# GD_Tcontroller_Front.net
KiCad netlist of a schematic drawn in Altium Designer
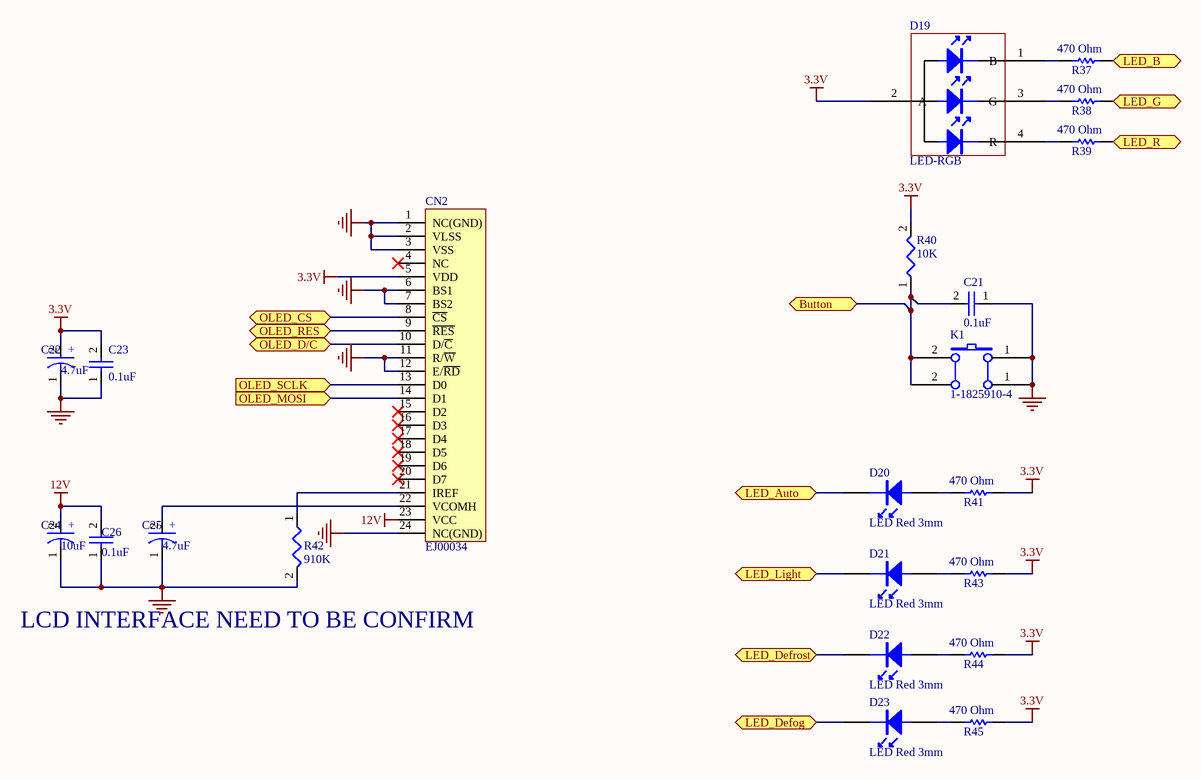
[diagram p0: GD_Tcontroller_Front.SchDoc]

(export (version "E")
  (design (tool "Eeschema 10.0.6"))
  (components
    (comp (ref "C21")
      (value "0.1uF")
      (footprint "C0805")
      (description "CAP SMD CR X7R 50V 10% 0.1uF 0805 ROHS")
      (fields (field (name "MANUFACTURER") "YAGEO") (field (name "Comment") "CAP"))
      (libsource (lib "enlogic") (part "CAP"))
    )
    (comp (ref "C22")
      (value "4.7uF")
      (footprint "TAN3216")
      (description "TAN 10uF 20% 10V 3216")
      (fields (field (name "MANUFACTURER") "AVX") (field (name "Comment") "CAPACITOR"))
      (libsource (lib "enlogic") (part "CAPACITOR"))
    )
    (comp (ref "C23")
      (value "0.1uF")
      (footprint "C0805")
      (description "CAP SMD CR X7R 50V 10% 0.1uF 0805 ROHS")
      (fields (field (name "MANUFACTURER") "YAGEO") (field (name "Comment") "CAP"))
      (libsource (lib "enlogic") (part "CAP"))
    )
    (comp (ref "C24")
      (value "10uF")
      (footprint "TAN6032")
      (description "CAP SMD Tan 35V 10% 10uF 2917 ROHS")
      (fields (field (name "MANUFACTURER") "AVX") (field (name "Comment") "CAPACITOR"))
      (libsource (lib "enlogic") (part "CAPACITOR"))
    )
    (comp (ref "C25")
      (value "4.7uF")
      (footprint "TAN6032")
      (description "CAP SMD Tan 35V 10% 4.7uF 2312 ROHS")
      (fields (field (name "MANUFACTURER") "AVX") (field (name "Comment") "CAPACITOR"))
      (libsource (lib "enlogic") (part "CAPACITOR"))
    )
    (comp (ref "C26")
      (value "0.1uF")
      (footprint "C0805")
      (description "CAP SMD CR X7R 50V 10% 0.1uF 0805 ROHS")
      (fields (field (name "MANUFACTURER") "YAGEO") (field (name "Comment") "CAP"))
      (libsource (lib "enlogic") (part "CAP"))
    )
    (comp (ref "CN2")
      (value "EJ00034")
      (footprint "PcbLib1:FPC24P0_5")
      (description "CONNECTOR FPC0.5MM 24PIN,0.4A,50V,SMT")
      (fields (field (name "MANUFACTURER") "FCI"))
      (libsource (lib "enlogic") (part "OLED_24-Pin"))
    )
    (comp (ref "D19")
      (value "LED-RGB")
      (footprint "LED-RGB-3528")
      (libsource (lib "Schlib1") (part "LED-RGB"))
    )
    (comp (ref "D20") (value "LED Red 3mm") (footprint "LED_DIP") (libsource (lib "*") (part "LED")))
    (comp (ref "D21") (value "LED Red 3mm") (footprint "LED_DIP") (libsource (lib "*") (part "LED")))
    (comp (ref "D22") (value "LED Red 3mm") (footprint "LED_DIP") (libsource (lib "*") (part "LED")))
    (comp (ref "D23") (value "LED Red 3mm") (footprint "LED_DIP") (libsource (lib "*") (part "LED")))
    (comp (ref "K1")
      (value "1-1825910-4")
      (footprint "AN6_3P6_5")
      (description "Button ON/OFF，6.3X6.3X9.5MM,DIP-2")
      (fields (field (name "MANUFACTURER") "Tyco Electronics") (field (name "Comment") "SW PUSHBUTTON"))
      (libsource (lib "enlogic") (part "SW PUSHBUTTON"))
    )
    (comp (ref "R37")
      (value "470 Ohm")
      (footprint "R0805")
      (description "470Ohm 0.125W 5% 0805 (2012 Metric)  SMD")
      (fields (field (name "POWER") "0.125 W") (field (name "TOLERANCE") "5 %"))
      (libsource (lib "Altium Content Vault") (part "CMP-1013-00098-1"))
    )
    (comp (ref "R38")
      (value "470 Ohm")
      (footprint "R0805")
      (description "470Ohm 0.125W 5% 0805 (2012 Metric)  SMD")
      (fields (field (name "POWER") "0.125 W") (field (name "TOLERANCE") "5 %"))
      (libsource (lib "Altium Content Vault") (part "CMP-1013-00098-1"))
    )
    (comp (ref "R39")
      (value "470 Ohm")
      (footprint "R0805")
      (description "470Ohm 0.125W 5% 0805 (2012 Metric)  SMD")
      (fields (field (name "POWER") "0.125 W") (field (name "TOLERANCE") "5 %"))
      (libsource (lib "Altium Content Vault") (part "CMP-1013-00098-1"))
    )
    (comp (ref "R40")
      (value "10K")
      (footprint "R0805")
      (description "RES THICK_FILM SMD 10K 5% 1/8W ROHS 0805")
      (fields (field (name "MANUFACTURER") "YAGEO") (field (name "Comment") "RES"))
      (libsource (lib "enlogic") (part "RES"))
    )
    (comp (ref "R41")
      (value "470 Ohm")
      (footprint "R0805")
      (description "470Ohm 0.125W 5% 0805 (2012 Metric)  SMD")
      (fields (field (name "POWER") "0.125 W") (field (name "TOLERANCE") "5 %"))
      (libsource (lib "Altium Content Vault") (part "CMP-1013-00098-1"))
    )
    (comp (ref "R42")
      (value "910K")
      (footprint "R0805")
      (description "RES 	THICK_FILM SMD 910K 1%	 1/8W 	ROHS 	0805")
      (fields (field (name "MANUFACTURER") "YAGEO") (field (name "Comment") "RES"))
      (libsource (lib "enlogic") (part "RES"))
    )
    (comp (ref "R43")
      (value "470 Ohm")
      (footprint "R0805")
      (description "470Ohm 0.125W 5% 0805 (2012 Metric)  SMD")
      (fields (field (name "POWER") "0.125 W") (field (name "TOLERANCE") "5 %"))
      (libsource (lib "Altium Content Vault") (part "CMP-1013-00098-1"))
    )
    (comp (ref "R44")
      (value "470 Ohm")
      (footprint "R0805")
      (description "470Ohm 0.125W 5% 0805 (2012 Metric)  SMD")
      (fields (field (name "POWER") "0.125 W") (field (name "TOLERANCE") "5 %"))
      (libsource (lib "Altium Content Vault") (part "CMP-1013-00098-1"))
    )
    (comp (ref "R45")
      (value "470 Ohm")
      (footprint "R0805")
      (description "470Ohm 0.125W 5% 0805 (2012 Metric)  SMD")
      (fields (field (name "POWER") "0.125 W") (field (name "TOLERANCE") "5 %"))
      (libsource (lib "Altium Content Vault") (part "CMP-1013-00098-1"))
    )
  )
  (nets
    (net (code "1") (name "/Button") (class "Default")
      (node (ref "C21") (pin "2") (pinfunction "2_2") (pintype "passive"))
      (node (ref "K1") (pin "2") (pinfunction "B0_2") (pintype "passive"))
      (node (ref "R40") (pin "1") (pinfunction "1_1") (pintype "passive"))
    )
    (net (code "2") (name "/LED_Auto") (class "Default")
      (node (ref "D20") (pin "2") (pinfunction "2_2") (pintype "passive"))
    )
    (net (code "3") (name "/LED_B") (class "Default")
      (node (ref "R37") (pin "2") (pinfunction "2_2") (pintype "passive"))
    )
    (net (code "4") (name "/LED_Defog") (class "Default")
      (node (ref "D23") (pin "2") (pinfunction "2_2") (pintype "passive"))
    )
    (net (code "5") (name "/LED_Defrost") (class "Default")
      (node (ref "D22") (pin "2") (pinfunction "2_2") (pintype "passive"))
    )
    (net (code "6") (name "/LED_G") (class "Default")
      (node (ref "R38") (pin "2") (pinfunction "2_2") (pintype "passive"))
    )
    (net (code "7") (name "/LED_Light") (class "Default")
      (node (ref "D21") (pin "2") (pinfunction "2_2") (pintype "passive"))
    )
    (net (code "8") (name "/LED_R") (class "Default")
      (node (ref "R39") (pin "2") (pinfunction "2_2") (pintype "passive"))
    )
    (net (code "9") (name "/OLED_CS") (class "Default")
      (node (ref "CN2") (pin "8") (pinfunction "~{CS}_8") (pintype "passive"))
    )
    (net (code "10") (name "/OLED_D{slash}C") (class "Default")
      (node (ref "CN2") (pin "10") (pinfunction "D/~{C}_10") (pintype "passive"))
    )
    (net (code "11") (name "/OLED_MOSI") (class "Default")
      (node (ref "CN2") (pin "14") (pinfunction "D1_14") (pintype "passive"))
    )
    (net (code "12") (name "/OLED_RES") (class "Default")
      (node (ref "CN2") (pin "9") (pinfunction "~{RES}_9") (pintype "passive"))
    )
    (net (code "13") (name "/OLED_SCLK") (class "Default")
      (node (ref "CN2") (pin "13") (pinfunction "D0_13") (pintype "passive"))
    )
    (net (code "14") (name "3.3V") (class "Default")
      (node (ref "C22") (pin "2") (pinfunction "2_2") (pintype "passive"))
      (node (ref "C23") (pin "2") (pinfunction "2_2") (pintype "passive"))
      (node (ref "CN2") (pin "5") (pinfunction "VDD_5") (pintype "passive"))
      (node (ref "D19") (pin "2") (pinfunction "A_2") (pintype "passive"))
      (node (ref "R40") (pin "2") (pinfunction "2_2") (pintype "passive"))
      (node (ref "R41") (pin "2") (pinfunction "2_2") (pintype "passive"))
      (node (ref "R43") (pin "2") (pinfunction "2_2") (pintype "passive"))
      (node (ref "R44") (pin "2") (pinfunction "2_2") (pintype "passive"))
      (node (ref "R45") (pin "2") (pinfunction "2_2") (pintype "passive"))
    )
    (net (code "15") (name "12V") (class "Default")
      (node (ref "C24") (pin "2") (pinfunction "2_2") (pintype "passive"))
      (node (ref "C26") (pin "2") (pinfunction "2_2") (pintype "passive"))
      (node (ref "CN2") (pin "23") (pinfunction "VCC_23") (pintype "passive"))
    )
    (net (code "16") (name "GND") (class "Default")
      (node (ref "C21") (pin "1") (pinfunction "1_1") (pintype "passive"))
      (node (ref "C22") (pin "1") (pinfunction "1_1") (pintype "passive"))
      (node (ref "C23") (pin "1") (pinfunction "1_1") (pintype "passive"))
      (node (ref "C24") (pin "1") (pinfunction "1_1") (pintype "passive"))
      (node (ref "C25") (pin "1") (pinfunction "1_1") (pintype "passive"))
      (node (ref "C26") (pin "1") (pinfunction "1_1") (pintype "passive"))
      (node (ref "CN2") (pin "1") (pinfunction "NC(GND)_1") (pintype "passive"))
      (node (ref "CN2") (pin "11") (pinfunction "R/~{W}_11") (pintype "passive"))
      (node (ref "CN2") (pin "12") (pinfunction "E/~{RD}_12") (pintype "passive"))
      (node (ref "CN2") (pin "2") (pinfunction "VLSS_2") (pintype "passive"))
      (node (ref "CN2") (pin "24") (pinfunction "NC(GND)_24") (pintype "passive"))
      (node (ref "CN2") (pin "3") (pinfunction "VSS_3") (pintype "passive"))
      (node (ref "CN2") (pin "6") (pinfunction "BS1_6") (pintype "passive"))
      (node (ref "CN2") (pin "7") (pinfunction "BS2_7") (pintype "passive"))
      (node (ref "K1") (pin "1") (pinfunction "A0_1") (pintype "passive"))
      (node (ref "R42") (pin "2") (pinfunction "2_2") (pintype "passive"))
    )
    (net (code "17") (name "Net-(CN2-IREF)") (class "Default")
      (node (ref "CN2") (pin "21") (pinfunction "IREF_21") (pintype "passive"))
      (node (ref "R42") (pin "1") (pinfunction "1_1") (pintype "passive"))
    )
    (net (code "18") (name "Net-(CN2-VCOMH)") (class "Default")
      (node (ref "C25") (pin "2") (pinfunction "2_2") (pintype "passive"))
      (node (ref "CN2") (pin "22") (pinfunction "VCOMH_22") (pintype "passive"))
    )
    (net (code "19") (name "Net-(D19-B)") (class "Default")
      (node (ref "D19") (pin "1") (pinfunction "B_1") (pintype "passive"))
      (node (ref "R37") (pin "1") (pinfunction "1_1") (pintype "passive"))
    )
    (net (code "20") (name "Net-(D19-G)") (class "Default")
      (node (ref "D19") (pin "3") (pinfunction "G_3") (pintype "passive"))
      (node (ref "R38") (pin "1") (pinfunction "1_1") (pintype "passive"))
    )
    (net (code "21") (name "Net-(D19-R)") (class "Default")
      (node (ref "D19") (pin "4") (pinfunction "R_4") (pintype "passive"))
      (node (ref "R39") (pin "1") (pinfunction "1_1") (pintype "passive"))
    )
    (net (code "22") (name "Net-(D20-Pad1)") (class "Default")
      (node (ref "D20") (pin "1") (pinfunction "1_1") (pintype "passive"))
      (node (ref "R41") (pin "1") (pinfunction "1_1") (pintype "passive"))
    )
    (net (code "23") (name "Net-(D21-Pad1)") (class "Default")
      (node (ref "D21") (pin "1") (pinfunction "1_1") (pintype "passive"))
      (node (ref "R43") (pin "1") (pinfunction "1_1") (pintype "passive"))
    )
    (net (code "24") (name "Net-(D22-Pad1)") (class "Default")
      (node (ref "D22") (pin "1") (pinfunction "1_1") (pintype "passive"))
      (node (ref "R44") (pin "1") (pinfunction "1_1") (pintype "passive"))
    )
    (net (code "25") (name "Net-(D23-Pad1)") (class "Default")
      (node (ref "D23") (pin "1") (pinfunction "1_1") (pintype "passive"))
      (node (ref "R45") (pin "1") (pinfunction "1_1") (pintype "passive"))
    )
    (net (code "26") (name "unconnected-(CN2-D2-Pad15)") (class "Default")
      (node (ref "CN2") (pin "15") (pinfunction "D2_15") (pintype "passive+no_connect"))
    )
    (net (code "27") (name "unconnected-(CN2-D3-Pad16)") (class "Default")
      (node (ref "CN2") (pin "16") (pinfunction "D3_16") (pintype "passive+no_connect"))
    )
    (net (code "28") (name "unconnected-(CN2-D4-Pad17)") (class "Default")
      (node (ref "CN2") (pin "17") (pinfunction "D4_17") (pintype "passive+no_connect"))
    )
    (net (code "29") (name "unconnected-(CN2-D5-Pad18)") (class "Default")
      (node (ref "CN2") (pin "18") (pinfunction "D5_18") (pintype "passive+no_connect"))
    )
    (net (code "30") (name "unconnected-(CN2-D6-Pad19)") (class "Default")
      (node (ref "CN2") (pin "19") (pinfunction "D6_19") (pintype "passive+no_connect"))
    )
    (net (code "31") (name "unconnected-(CN2-D7-Pad20)") (class "Default")
      (node (ref "CN2") (pin "20") (pinfunction "D7_20") (pintype "passive+no_connect"))
    )
    (net (code "32") (name "unconnected-(CN2-NC-Pad4)") (class "Default")
      (node (ref "CN2") (pin "4") (pinfunction "NC_4") (pintype "passive+no_connect"))
    )
  )
)
